# Ethernet_Board.net
KiCad netlist of a schematic drawn in EAGLE
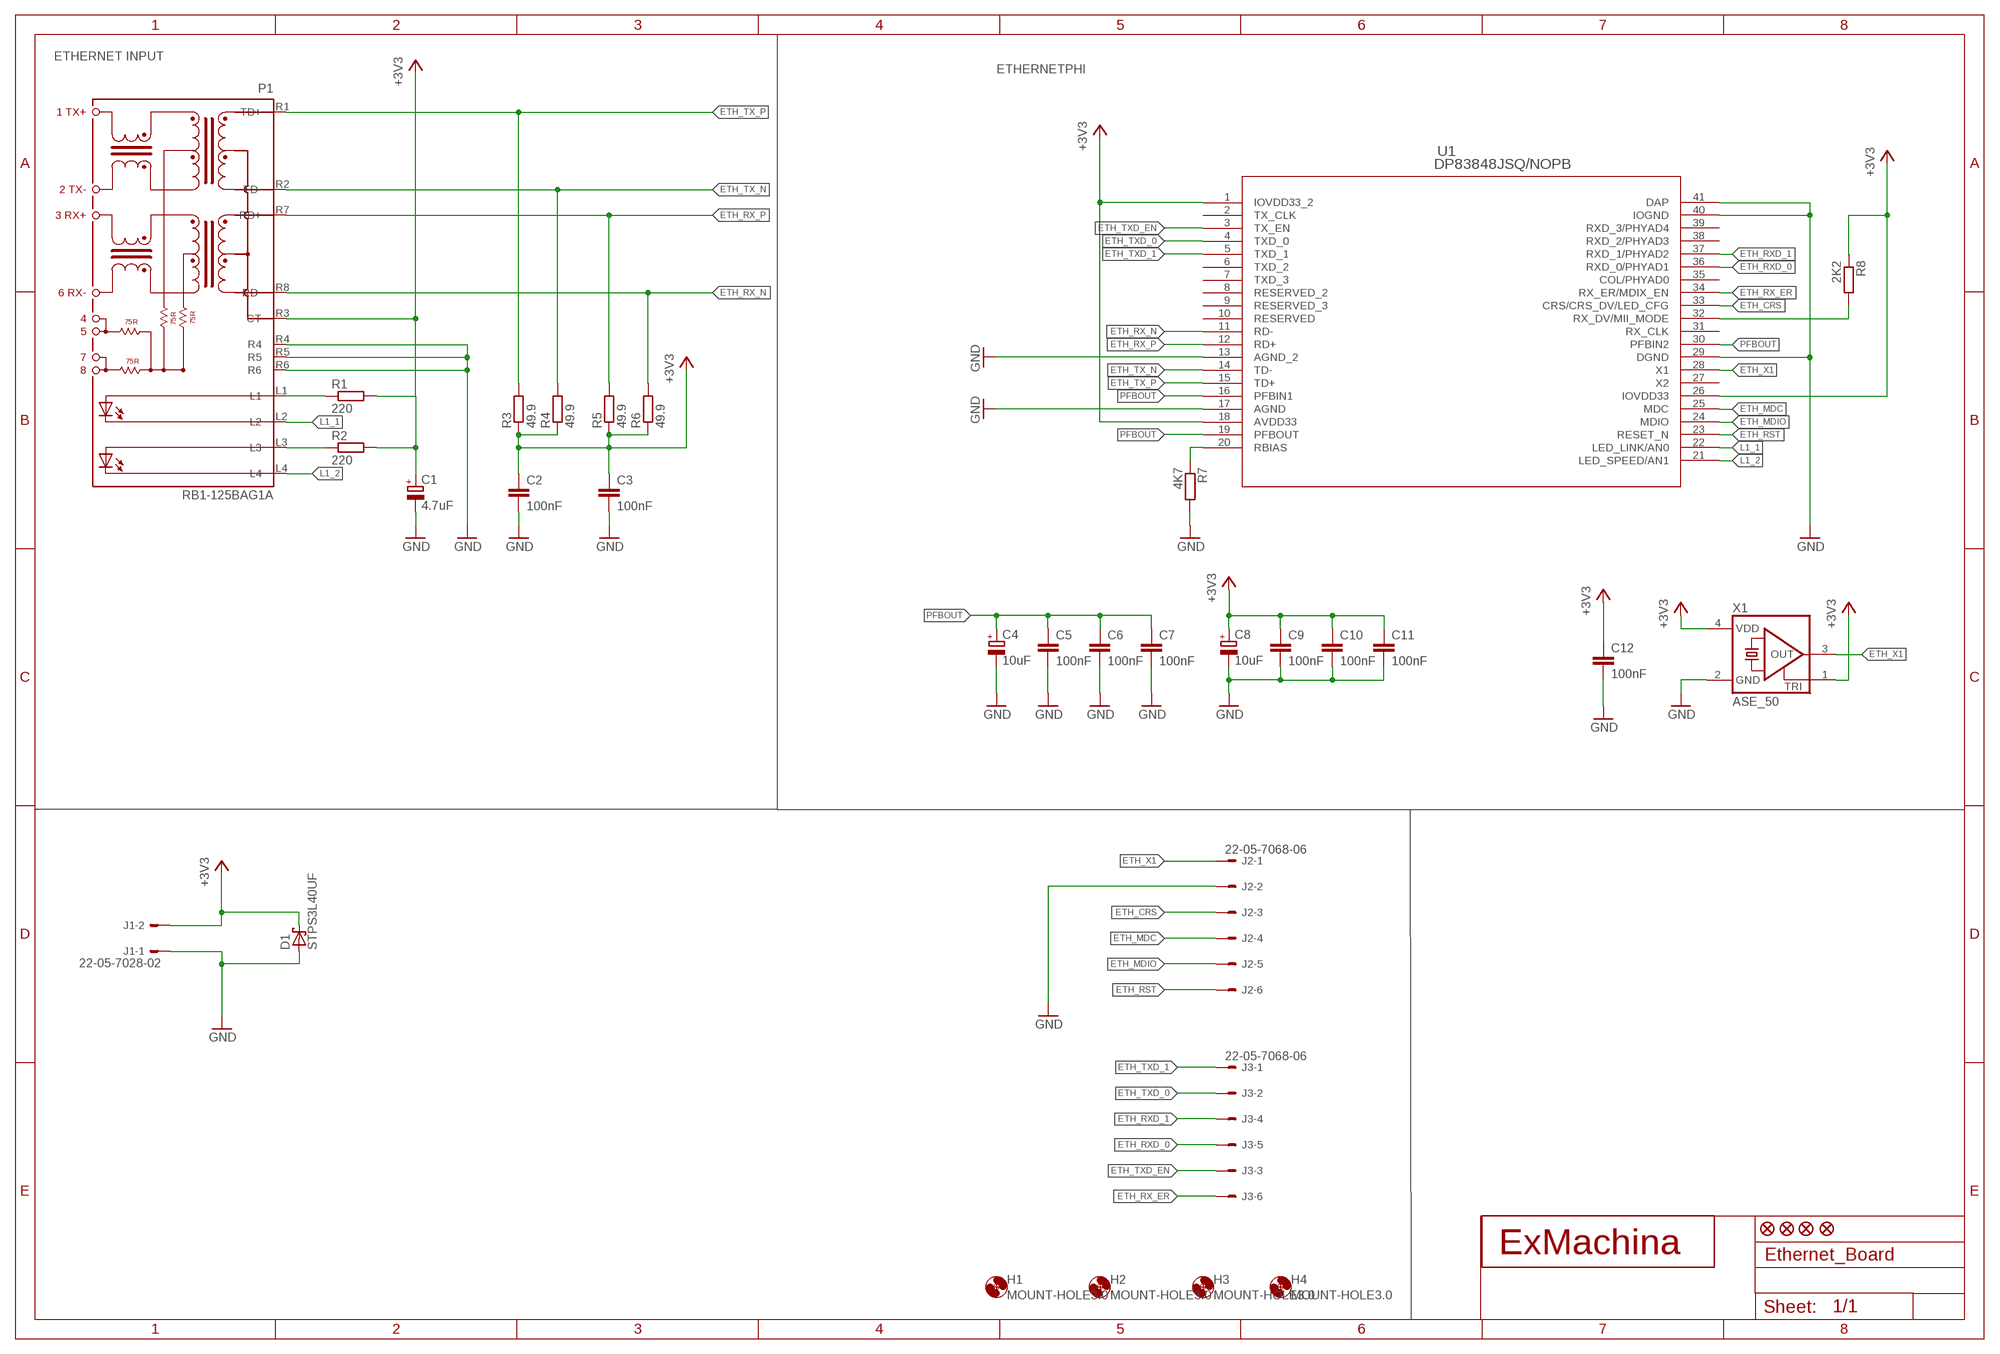
[diagram p0: schematic, sheet 1]

(export (version "E")
  (design (tool "Eeschema 10.0.6"))
  (components
    (comp (ref "C1")
      (value "4.7uF")
      (footprint "eagle-import:CT3216")
      (libsource (lib "eagle-import") (part "CPOL-EUCT3216"))
    )
    (comp (ref "C2")
      (value "100nF")
      (footprint "eagle-import:C0603")
      (libsource (lib "eagle-import") (part "C-EUC0603"))
    )
    (comp (ref "C3")
      (value "100nF")
      (footprint "eagle-import:C0603")
      (libsource (lib "eagle-import") (part "C-EUC0603"))
    )
    (comp (ref "C4")
      (value "10uF")
      (footprint "eagle-import:CT3216")
      (libsource (lib "eagle-import") (part "CPOL-EUCT3216"))
    )
    (comp (ref "C5")
      (value "100nF")
      (footprint "eagle-import:C0603")
      (libsource (lib "eagle-import") (part "C-EUC0603"))
    )
    (comp (ref "C6")
      (value "100nF")
      (footprint "eagle-import:C0603")
      (libsource (lib "eagle-import") (part "C-EUC0603"))
    )
    (comp (ref "C7")
      (value "100nF")
      (footprint "eagle-import:C0603")
      (libsource (lib "eagle-import") (part "C-EUC0603"))
    )
    (comp (ref "C8")
      (value "10uF")
      (footprint "eagle-import:CT3216")
      (libsource (lib "eagle-import") (part "CPOL-EUCT3216"))
    )
    (comp (ref "C9")
      (value "100nF")
      (footprint "eagle-import:C0603")
      (libsource (lib "eagle-import") (part "C-EUC0603"))
    )
    (comp (ref "C10")
      (value "100nF")
      (footprint "eagle-import:C0603")
      (libsource (lib "eagle-import") (part "C-EUC0603"))
    )
    (comp (ref "C11")
      (value "100nF")
      (footprint "eagle-import:C0603")
      (libsource (lib "eagle-import") (part "C-EUC0603"))
    )
    (comp (ref "C12")
      (value "100nF")
      (footprint "eagle-import:C0603")
      (libsource (lib "eagle-import") (part "C-EUC0603"))
    )
    (comp (ref "D1")
      (value "STPS3L40UF")
      (footprint "eagle-import:SMB")
      (fields (field (name "MP") "STMICROELECTRONICS"))
      (libsource (lib "eagle-import") (part "STPS3L40?UF"))
    )
    (comp (ref "H1")
      (value "MOUNT-HOLE3.0")
      (footprint "eagle-import:3,0")
      (libsource (lib "eagle-import") (part "MOUNT-HOLE3.0"))
    )
    (comp (ref "H2")
      (value "MOUNT-HOLE3.0")
      (footprint "eagle-import:3,0")
      (libsource (lib "eagle-import") (part "MOUNT-HOLE3.0"))
    )
    (comp (ref "H3")
      (value "MOUNT-HOLE3.0")
      (footprint "eagle-import:3,0")
      (libsource (lib "eagle-import") (part "MOUNT-HOLE3.0"))
    )
    (comp (ref "H4")
      (value "MOUNT-HOLE3.0")
      (footprint "eagle-import:3,0")
      (libsource (lib "eagle-import") (part "MOUNT-HOLE3.0"))
    )
    (comp (ref "J1")
      (value "22-05-7028-02")
      (footprint "eagle-import:7395-02")
      (libsource (lib "eagle-import") (part "22-?-0205-7028"))
    )
    (comp (ref "J2")
      (value "22-05-7068-06")
      (footprint "eagle-import:7395-06")
      (libsource (lib "eagle-import") (part "22-?-0605-7068"))
    )
    (comp (ref "J3")
      (value "22-05-7068-06")
      (footprint "eagle-import:7395-06")
      (libsource (lib "eagle-import") (part "22-?-0605-7068"))
    )
    (comp (ref "JP1")
      (value "FIDUCIAL1X2")
      (footprint "eagle-import:FIDUCIAL-1X2")
      (libsource (lib "eagle-import") (part "FIDUCIAL1X2"))
    )
    (comp (ref "JP2")
      (value "FIDUCIAL1X2")
      (footprint "eagle-import:FIDUCIAL-1X2")
      (libsource (lib "eagle-import") (part "FIDUCIAL1X2"))
    )
    (comp (ref "JP3")
      (value "FIDUCIAL1X2")
      (footprint "eagle-import:FIDUCIAL-1X2")
      (libsource (lib "eagle-import") (part "FIDUCIAL1X2"))
    )
    (comp (ref "JP4")
      (value "FIDUCIAL1X2")
      (footprint "eagle-import:FIDUCIAL-1X2")
      (libsource (lib "eagle-import") (part "FIDUCIAL1X2"))
    )
    (comp (ref "P1")
      (value "RB1-125BAG1A")
      (footprint "eagle-import:WIZNET_RB1-125BAG1A")
      (libsource (lib "eagle-import") (part "RB1-125BAG1A"))
    )
    (comp (ref "R1")
      (value "220")
      (footprint "eagle-import:R0603")
      (libsource (lib "eagle-import") (part "R-EU_R0603"))
    )
    (comp (ref "R2")
      (value "220")
      (footprint "eagle-import:R0603")
      (libsource (lib "eagle-import") (part "R-EU_R0603"))
    )
    (comp (ref "R3")
      (value "49.9")
      (footprint "eagle-import:R0603")
      (libsource (lib "eagle-import") (part "R-EU_R0603"))
    )
    (comp (ref "R4")
      (value "49.9")
      (footprint "eagle-import:R0603")
      (libsource (lib "eagle-import") (part "R-EU_R0603"))
    )
    (comp (ref "R5")
      (value "49.9")
      (footprint "eagle-import:R0603")
      (libsource (lib "eagle-import") (part "R-EU_R0603"))
    )
    (comp (ref "R6")
      (value "49.9")
      (footprint "eagle-import:R0603")
      (libsource (lib "eagle-import") (part "R-EU_R0603"))
    )
    (comp (ref "R7")
      (value "4K7")
      (footprint "eagle-import:R0603")
      (libsource (lib "eagle-import") (part "R-EU_R0603"))
    )
    (comp (ref "R8")
      (value "2K2")
      (footprint "eagle-import:R0603")
      (libsource (lib "eagle-import") (part "R-EU_R0603"))
    )
    (comp (ref "T1")
      (value "EXMACHINA-LOGO-NAME")
      (footprint "eagle-import:EXM-LOGO-BASELINE")
      (libsource (lib "eagle-import") (part "EXMACHINA-LOGO-NAME"))
    )
    (comp (ref "U1")
      (value "DP83848JSQ/NOPB")
      (footprint "eagle-import:SQA40B")
      (fields
        (field (name "MANUFACTURER_PART_NUMBER") "dp83848jsqnopb")
        (field (name "COPYRIGHT") "Copyright C 2015 Accelerated Designs. All rights reserved")
      )
      (libsource (lib "eagle-import") (part "DP83848JSQ/NOPB"))
    )
    (comp (ref "X1")
      (value "ASE_50")
      (footprint "eagle-import:ASE")
      (libsource (lib "eagle-import") (part "ASE"))
    )
  )
  (nets
    (net (code "1") (name "+3V3") (class "Default")
      (node (ref "C1") (pin "+") (pinfunction "+_+") (pintype "passive"))
      (node (ref "C10") (pin "1") (pinfunction "1_1") (pintype "passive"))
      (node (ref "C11") (pin "1") (pinfunction "1_1") (pintype "passive"))
      (node (ref "C12") (pin "1") (pinfunction "1_1") (pintype "passive"))
      (node (ref "C2") (pin "1") (pinfunction "1_1") (pintype "passive"))
      (node (ref "C3") (pin "1") (pinfunction "1_1") (pintype "passive"))
      (node (ref "C8") (pin "+") (pinfunction "+_+") (pintype "passive"))
      (node (ref "C9") (pin "1") (pinfunction "1_1") (pintype "passive"))
      (node (ref "D1") (pin "C") (pinfunction "C_C") (pintype "passive"))
      (node (ref "J1") (pin "2") (pinfunction "S_2") (pintype "passive"))
      (node (ref "P1") (pin "R3") (pinfunction "CT_R3") (pintype "input"))
      (node (ref "R1") (pin "2") (pinfunction "2_2") (pintype "passive"))
      (node (ref "R2") (pin "2") (pinfunction "2_2") (pintype "passive"))
      (node (ref "R3") (pin "1") (pinfunction "1_1") (pintype "passive"))
      (node (ref "R4") (pin "1") (pinfunction "1_1") (pintype "passive"))
      (node (ref "R5") (pin "1") (pinfunction "1_1") (pintype "passive"))
      (node (ref "R6") (pin "1") (pinfunction "1_1") (pintype "passive"))
      (node (ref "R8") (pin "1") (pinfunction "1_1") (pintype "passive"))
      (node (ref "U1") (pin "1") (pinfunction "IOVDD33_2_1") (pintype "power_in"))
      (node (ref "U1") (pin "18") (pinfunction "AVDD33_18") (pintype "power_in"))
      (node (ref "U1") (pin "26") (pinfunction "IOVDD33_26") (pintype "power_in"))
      (node (ref "X1") (pin "1") (pinfunction "TRI_1") (pintype "input"))
      (node (ref "X1") (pin "4") (pinfunction "VDD_4") (pintype "power_in"))
    )
    (net (code "2") (name "ETH_CRS") (class "Default")
      (node (ref "J2") (pin "3") (pinfunction "S_3") (pintype "passive"))
      (node (ref "U1") (pin "33") (pinfunction "CRS/CRS_DV/LED_CFG_33") (pintype "output"))
    )
    (net (code "3") (name "ETH_MDC") (class "Default")
      (node (ref "J2") (pin "4") (pinfunction "S_4") (pintype "passive"))
      (node (ref "U1") (pin "25") (pinfunction "MDC_25") (pintype "input"))
    )
    (net (code "4") (name "ETH_MDIO") (class "Default")
      (node (ref "J2") (pin "5") (pinfunction "S_5") (pintype "passive"))
      (node (ref "U1") (pin "24") (pinfunction "MDIO_24") (pintype "bidirectional"))
    )
    (net (code "5") (name "ETH_RST") (class "Default")
      (node (ref "J2") (pin "6") (pinfunction "S_6") (pintype "passive"))
      (node (ref "U1") (pin "23") (pinfunction "RESET_N_23") (pintype "input"))
    )
    (net (code "6") (name "ETH_RXD_0") (class "Default")
      (node (ref "J3") (pin "5") (pinfunction "S_5") (pintype "passive"))
      (node (ref "U1") (pin "36") (pinfunction "RXD_0/PHYAD1_36") (pintype "output"))
    )
    (net (code "7") (name "ETH_RXD_1") (class "Default")
      (node (ref "J3") (pin "4") (pinfunction "S_4") (pintype "passive"))
      (node (ref "U1") (pin "37") (pinfunction "RXD_1/PHYAD2_37") (pintype "output"))
    )
    (net (code "8") (name "ETH_RX_ER") (class "Default")
      (node (ref "J3") (pin "6") (pinfunction "S_6") (pintype "passive"))
      (node (ref "U1") (pin "34") (pinfunction "RX_ER/MDIX_EN_34") (pintype "output"))
    )
    (net (code "9") (name "ETH_RX_N") (class "Default")
      (node (ref "P1") (pin "R8") (pinfunction "RD-_R8") (pintype "input"))
      (node (ref "R6") (pin "2") (pinfunction "2_2") (pintype "passive"))
      (node (ref "U1") (pin "11") (pinfunction "RD-_11") (pintype "bidirectional"))
    )
    (net (code "10") (name "ETH_RX_P") (class "Default")
      (node (ref "P1") (pin "R7") (pinfunction "RD+_R7") (pintype "input"))
      (node (ref "R5") (pin "2") (pinfunction "2_2") (pintype "passive"))
      (node (ref "U1") (pin "12") (pinfunction "RD+_12") (pintype "bidirectional"))
    )
    (net (code "11") (name "ETH_TXD_0") (class "Default")
      (node (ref "J3") (pin "2") (pinfunction "S_2") (pintype "passive"))
      (node (ref "U1") (pin "4") (pinfunction "TXD_0_4") (pintype "input"))
    )
    (net (code "12") (name "ETH_TXD_1") (class "Default")
      (node (ref "J3") (pin "1") (pinfunction "S_1") (pintype "passive"))
      (node (ref "U1") (pin "5") (pinfunction "TXD_1_5") (pintype "input"))
    )
    (net (code "13") (name "ETH_TXD_EN") (class "Default")
      (node (ref "J3") (pin "3") (pinfunction "S_3") (pintype "passive"))
      (node (ref "U1") (pin "3") (pinfunction "TX_EN_3") (pintype "input"))
    )
    (net (code "14") (name "ETH_TX_N") (class "Default")
      (node (ref "P1") (pin "R2") (pinfunction "TD-_R2") (pintype "input"))
      (node (ref "R4") (pin "2") (pinfunction "2_2") (pintype "passive"))
      (node (ref "U1") (pin "14") (pinfunction "TD-_14") (pintype "bidirectional"))
    )
    (net (code "15") (name "ETH_TX_P") (class "Default")
      (node (ref "P1") (pin "R1") (pinfunction "TD+_R1") (pintype "input"))
      (node (ref "R3") (pin "2") (pinfunction "2_2") (pintype "passive"))
      (node (ref "U1") (pin "15") (pinfunction "TD+_15") (pintype "bidirectional"))
    )
    (net (code "16") (name "ETH_X1") (class "Default")
      (node (ref "J2") (pin "1") (pinfunction "S_1") (pintype "passive"))
      (node (ref "U1") (pin "28") (pinfunction "X1_28") (pintype "input"))
      (node (ref "X1") (pin "3") (pinfunction "OUT_3") (pintype "output"))
    )
    (net (code "17") (name "GND") (class "Default")
      (node (ref "C1") (pin "-") (pinfunction "-_-") (pintype "passive"))
      (node (ref "C10") (pin "2") (pinfunction "2_2") (pintype "passive"))
      (node (ref "C11") (pin "2") (pinfunction "2_2") (pintype "passive"))
      (node (ref "C12") (pin "2") (pinfunction "2_2") (pintype "passive"))
      (node (ref "C2") (pin "2") (pinfunction "2_2") (pintype "passive"))
      (node (ref "C3") (pin "2") (pinfunction "2_2") (pintype "passive"))
      (node (ref "C4") (pin "-") (pinfunction "-_-") (pintype "passive"))
      (node (ref "C5") (pin "2") (pinfunction "2_2") (pintype "passive"))
      (node (ref "C6") (pin "2") (pinfunction "2_2") (pintype "passive"))
      (node (ref "C7") (pin "2") (pinfunction "2_2") (pintype "passive"))
      (node (ref "C8") (pin "-") (pinfunction "-_-") (pintype "passive"))
      (node (ref "C9") (pin "2") (pinfunction "2_2") (pintype "passive"))
      (node (ref "D1") (pin "A") (pinfunction "A_A") (pintype "passive"))
      (node (ref "J1") (pin "1") (pinfunction "S_1") (pintype "passive"))
      (node (ref "J2") (pin "2") (pinfunction "S_2") (pintype "passive"))
      (node (ref "P1") (pin "R4") (pinfunction "R4_R4") (pintype "input"))
      (node (ref "P1") (pin "R5") (pinfunction "R5_R5") (pintype "input"))
      (node (ref "P1") (pin "R6") (pinfunction "R6_R6") (pintype "input"))
      (node (ref "R7") (pin "2") (pinfunction "2_2") (pintype "passive"))
      (node (ref "U1") (pin "13") (pinfunction "AGND_2_13") (pintype "power_in"))
      (node (ref "U1") (pin "17") (pinfunction "AGND_17") (pintype "power_in"))
      (node (ref "U1") (pin "29") (pinfunction "DGND_29") (pintype "power_in"))
      (node (ref "U1") (pin "40") (pinfunction "IOGND_40") (pintype "power_in"))
      (node (ref "U1") (pin "41") (pinfunction "DAP_41") (pintype "passive"))
      (node (ref "X1") (pin "2") (pinfunction "GND_2") (pintype "power_in"))
    )
    (net (code "18") (name "L1_1") (class "Default")
      (node (ref "P1") (pin "L2") (pinfunction "L2_L2") (pintype "passive"))
      (node (ref "U1") (pin "22") (pinfunction "LED_LINK/AN0_22") (pintype "output"))
    )
    (net (code "19") (name "L1_2") (class "Default")
      (node (ref "P1") (pin "L4") (pinfunction "L4_L4") (pintype "passive"))
      (node (ref "U1") (pin "21") (pinfunction "LED_SPEED/AN1_21") (pintype "output"))
    )
    (net (code "20") (name "Net-(P1-PadL1)") (class "Default")
      (node (ref "P1") (pin "L1") (pinfunction "L1_L1") (pintype "passive"))
      (node (ref "R1") (pin "1") (pinfunction "1_1") (pintype "passive"))
    )
    (net (code "21") (name "Net-(P1-PadL3)") (class "Default")
      (node (ref "P1") (pin "L3") (pinfunction "L3_L3") (pintype "passive"))
      (node (ref "R2") (pin "1") (pinfunction "1_1") (pintype "passive"))
    )
    (net (code "22") (name "Net-(U1-RBIAS)") (class "Default")
      (node (ref "R7") (pin "1") (pinfunction "1_1") (pintype "passive"))
      (node (ref "U1") (pin "20") (pinfunction "RBIAS_20") (pintype "input"))
    )
    (net (code "23") (name "Net-(U1-RX_DV{slash}MII_MODE)") (class "Default")
      (node (ref "R8") (pin "2") (pinfunction "2_2") (pintype "passive"))
      (node (ref "U1") (pin "32") (pinfunction "RX_DV/MII_MODE_32") (pintype "output"))
    )
    (net (code "24") (name "PFBOUT") (class "Default")
      (node (ref "C4") (pin "+") (pinfunction "+_+") (pintype "passive"))
      (node (ref "C5") (pin "1") (pinfunction "1_1") (pintype "passive"))
      (node (ref "C6") (pin "1") (pinfunction "1_1") (pintype "passive"))
      (node (ref "C7") (pin "1") (pinfunction "1_1") (pintype "passive"))
      (node (ref "U1") (pin "16") (pinfunction "PFBIN1_16") (pintype "input"))
      (node (ref "U1") (pin "19") (pinfunction "PFBOUT_19") (pintype "output"))
      (node (ref "U1") (pin "30") (pinfunction "PFBIN2_30") (pintype "input"))
    )
    (net (code "25") (name "unconnected-(U1-COL{slash}PHYAD0-Pad35)") (class "Default")
      (node (ref "U1") (pin "35") (pinfunction "COL/PHYAD0_35") (pintype "output"))
    )
    (net (code "26") (name "unconnected-(U1-RESERVED-Pad10)") (class "Default")
      (node (ref "U1") (pin "10") (pinfunction "RESERVED_10") (pintype "bidirectional"))
    )
    (net (code "27") (name "unconnected-(U1-RESERVED_2-Pad8)") (class "Default")
      (node (ref "U1") (pin "8") (pinfunction "RESERVED_2_8") (pintype "bidirectional"))
    )
    (net (code "28") (name "unconnected-(U1-RESERVED_3-Pad9)") (class "Default")
      (node (ref "U1") (pin "9") (pinfunction "RESERVED_3_9") (pintype "bidirectional"))
    )
    (net (code "29") (name "unconnected-(U1-RXD_2{slash}PHYAD3-Pad38)") (class "Default")
      (node (ref "U1") (pin "38") (pinfunction "RXD_2/PHYAD3_38") (pintype "output"))
    )
    (net (code "30") (name "unconnected-(U1-RXD_3{slash}PHYAD4-Pad39)") (class "Default")
      (node (ref "U1") (pin "39") (pinfunction "RXD_3/PHYAD4_39") (pintype "output"))
    )
    (net (code "31") (name "unconnected-(U1-RX_CLK-Pad31)") (class "Default")
      (node (ref "U1") (pin "31") (pinfunction "RX_CLK_31") (pintype "output"))
    )
    (net (code "32") (name "unconnected-(U1-TXD_2-Pad6)") (class "Default")
      (node (ref "U1") (pin "6") (pinfunction "TXD_2_6") (pintype "input"))
    )
    (net (code "33") (name "unconnected-(U1-TXD_3-Pad7)") (class "Default")
      (node (ref "U1") (pin "7") (pinfunction "TXD_3_7") (pintype "input"))
    )
    (net (code "34") (name "unconnected-(U1-TX_CLK-Pad2)") (class "Default")
      (node (ref "U1") (pin "2") (pinfunction "TX_CLK_2") (pintype "output"))
    )
    (net (code "35") (name "unconnected-(U1-X2-Pad27)") (class "Default")
      (node (ref "U1") (pin "27") (pinfunction "X2_27") (pintype "output"))
    )
  )
)
